# buffers_5bits.net
KiCad netlist of a schematic drawn in Altium Designer
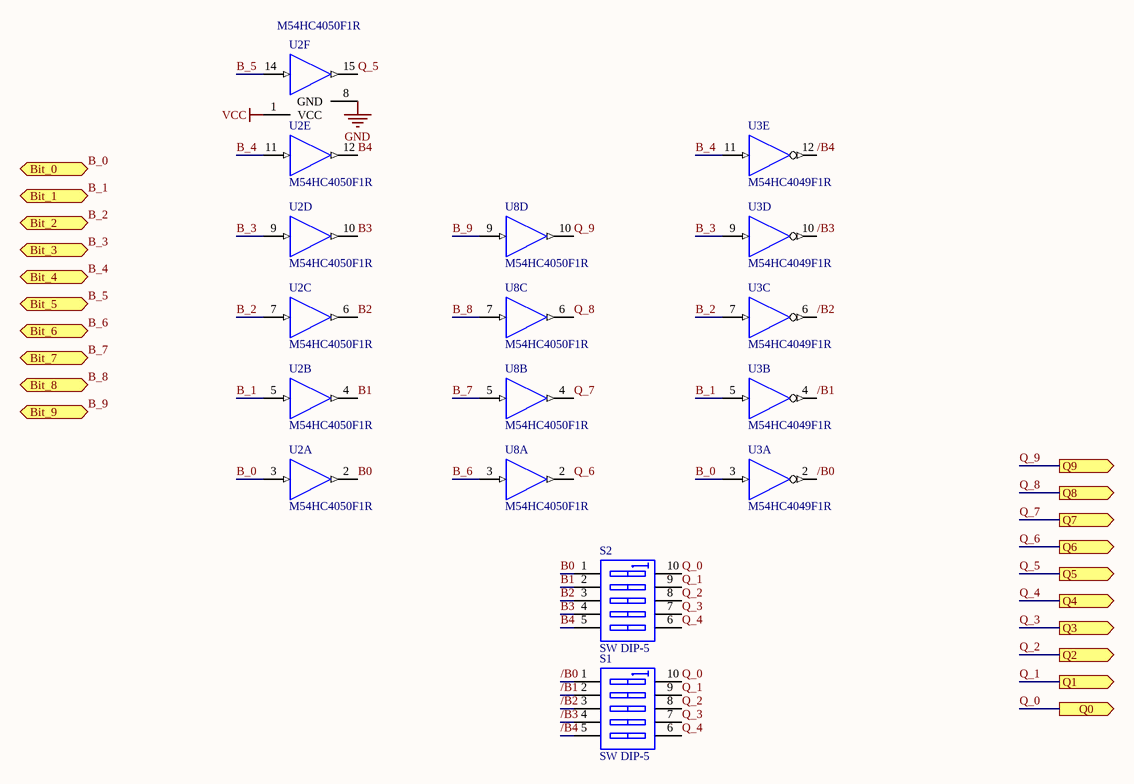
[diagram p0: buffers_5bits.SchDoc]

(export (version "E")
  (design (tool "Eeschema 10.0.6"))
  (components
    (comp (ref "S1")
      (value "SW DIP-5")
      (footprint "N10A")
      (description "DIP Switch, 5 Position, SPST")
      (fields (field (name "PUBLISHER") "Altium Limited"))
      (libsource (lib "Miscellaneous Devices") (part "SW DIP-5"))
    )
    (comp (ref "S2")
      (value "SW DIP-5")
      (footprint "N10A")
      (description "DIP Switch, 5 Position, SPST")
      (fields (field (name "PUBLISHER") "Altium Limited"))
      (libsource (lib "Miscellaneous Devices") (part "SW DIP-5"))
    )
    (comp (ref "U2")
      (value "M54HC4050F1R")
      (footprint "DIP16")
      (description "Hex Buffer/Converter Non-Inverting")
      (fields (field (name "PUBLISHER") "Altium Limited"))
      (libsource (lib "") (part "M54HC4050F1R_1"))
    )
    (comp (ref "U3")
      (value "M54HC4049F1R")
      (footprint "DIP16")
      (description "Hex Buffer/Converter Invertering")
      (fields (field (name "PUBLISHER") "Altium Limited"))
      (libsource (lib "ST Logic Gate") (part "M54HC4049F1R"))
    )
    (comp (ref "U8")
      (value "M54HC4050F1R")
      (footprint "DIP16")
      (description "Hex Buffer/Converter Non-Inverting")
      (fields (field (name "PUBLISHER") "Altium Limited"))
      (libsource (lib "ST Logic Gate") (part "M54HC4050F1R"))
    )
  )
  (nets
    (net (code "1") (name "/B0") (class "Default")
      (node (ref "S2") (pin "1") (pinfunction "A1_1") (pintype "passive"))
      (node (ref "U2") (pin "2") (pinfunction "Y_2") (pintype "output"))
    )
    (net (code "2") (name "/B1") (class "Default")
      (node (ref "S2") (pin "2") (pinfunction "A2_2") (pintype "passive"))
      (node (ref "U2") (pin "4") (pinfunction "Y_4") (pintype "output"))
    )
    (net (code "3") (name "/B2") (class "Default")
      (node (ref "S2") (pin "3") (pinfunction "A3_3") (pintype "passive"))
      (node (ref "U2") (pin "6") (pinfunction "Y_6") (pintype "output"))
    )
    (net (code "4") (name "/B3") (class "Default")
      (node (ref "S2") (pin "4") (pinfunction "A4_4") (pintype "passive"))
      (node (ref "U2") (pin "10") (pinfunction "Y_10") (pintype "output"))
    )
    (net (code "5") (name "/B4") (class "Default")
      (node (ref "S2") (pin "5") (pinfunction "A5_5") (pintype "passive"))
      (node (ref "U2") (pin "12") (pinfunction "Y_12") (pintype "output"))
    )
    (net (code "6") (name "/B_0") (class "Default")
      (node (ref "U2") (pin "3") (pinfunction "A_3") (pintype "input"))
      (node (ref "U3") (pin "3") (pinfunction "A_3") (pintype "input"))
    )
    (net (code "7") (name "/B_1") (class "Default")
      (node (ref "U2") (pin "5") (pinfunction "A_5") (pintype "input"))
      (node (ref "U3") (pin "5") (pinfunction "A_5") (pintype "input"))
    )
    (net (code "8") (name "/B_2") (class "Default")
      (node (ref "U2") (pin "7") (pinfunction "A_7") (pintype "input"))
      (node (ref "U3") (pin "7") (pinfunction "A_7") (pintype "input"))
    )
    (net (code "9") (name "/B_3") (class "Default")
      (node (ref "U2") (pin "9") (pinfunction "A_9") (pintype "input"))
      (node (ref "U3") (pin "9") (pinfunction "A_9") (pintype "input"))
    )
    (net (code "10") (name "/B_4") (class "Default")
      (node (ref "U2") (pin "11") (pinfunction "A_11") (pintype "input"))
      (node (ref "U3") (pin "11") (pinfunction "A_11") (pintype "input"))
    )
    (net (code "11") (name "/B_5") (class "Default")
      (node (ref "U2") (pin "14") (pinfunction "A_14") (pintype "input"))
    )
    (net (code "12") (name "/B_6") (class "Default")
      (node (ref "U8") (pin "3") (pinfunction "A_3") (pintype "input"))
    )
    (net (code "13") (name "/B_7") (class "Default")
      (node (ref "U8") (pin "5") (pinfunction "A_5") (pintype "input"))
    )
    (net (code "14") (name "/B_8") (class "Default")
      (node (ref "U8") (pin "7") (pinfunction "A_7") (pintype "input"))
    )
    (net (code "15") (name "/B_9") (class "Default")
      (node (ref "U8") (pin "9") (pinfunction "A_9") (pintype "input"))
    )
    (net (code "16") (name "/Q_0") (class "Default")
      (node (ref "S1") (pin "10") (pinfunction "B1_10") (pintype "passive"))
      (node (ref "S2") (pin "10") (pinfunction "B1_10") (pintype "passive"))
    )
    (net (code "17") (name "/Q_1") (class "Default")
      (node (ref "S1") (pin "9") (pinfunction "B2_9") (pintype "passive"))
      (node (ref "S2") (pin "9") (pinfunction "B2_9") (pintype "passive"))
    )
    (net (code "18") (name "/Q_2") (class "Default")
      (node (ref "S1") (pin "8") (pinfunction "B3_8") (pintype "passive"))
      (node (ref "S2") (pin "8") (pinfunction "B3_8") (pintype "passive"))
    )
    (net (code "19") (name "/Q_3") (class "Default")
      (node (ref "S1") (pin "7") (pinfunction "B4_7") (pintype "passive"))
      (node (ref "S2") (pin "7") (pinfunction "B4_7") (pintype "passive"))
    )
    (net (code "20") (name "/Q_4") (class "Default")
      (node (ref "S1") (pin "6") (pinfunction "B5_6") (pintype "passive"))
      (node (ref "S2") (pin "6") (pinfunction "B5_6") (pintype "passive"))
    )
    (net (code "21") (name "/Q_5") (class "Default")
      (node (ref "U2") (pin "15") (pinfunction "Y_15") (pintype "output"))
    )
    (net (code "22") (name "/Q_6") (class "Default")
      (node (ref "U8") (pin "2") (pinfunction "Y_2") (pintype "output"))
    )
    (net (code "23") (name "/Q_7") (class "Default")
      (node (ref "U8") (pin "4") (pinfunction "Y_4") (pintype "output"))
    )
    (net (code "24") (name "/Q_8") (class "Default")
      (node (ref "U8") (pin "6") (pinfunction "Y_6") (pintype "output"))
    )
    (net (code "25") (name "/Q_9") (class "Default")
      (node (ref "U8") (pin "10") (pinfunction "Y_10") (pintype "output"))
    )
    (net (code "26") (name "/{slash}B0") (class "Default")
      (node (ref "S1") (pin "1") (pinfunction "A1_1") (pintype "passive"))
      (node (ref "U3") (pin "2") (pinfunction "Y_2") (pintype "output"))
    )
    (net (code "27") (name "/{slash}B1") (class "Default")
      (node (ref "S1") (pin "2") (pinfunction "A2_2") (pintype "passive"))
      (node (ref "U3") (pin "4") (pinfunction "Y_4") (pintype "output"))
    )
    (net (code "28") (name "/{slash}B2") (class "Default")
      (node (ref "S1") (pin "3") (pinfunction "A3_3") (pintype "passive"))
      (node (ref "U3") (pin "6") (pinfunction "Y_6") (pintype "output"))
    )
    (net (code "29") (name "/{slash}B3") (class "Default")
      (node (ref "S1") (pin "4") (pinfunction "A4_4") (pintype "passive"))
      (node (ref "U3") (pin "10") (pinfunction "Y_10") (pintype "output"))
    )
    (net (code "30") (name "/{slash}B4") (class "Default")
      (node (ref "S1") (pin "5") (pinfunction "A5_5") (pintype "passive"))
      (node (ref "U3") (pin "12") (pinfunction "Y_12") (pintype "output"))
    )
    (net (code "31") (name "GND") (class "Default")
      (node (ref "U2") (pin "8") (pinfunction "GND_8") (pintype "power_in"))
      (node (ref "U3") (pin "8") (pinfunction "GND_8") (pintype "power_in"))
      (node (ref "U8") (pin "8") (pinfunction "GND_8") (pintype "power_in"))
    )
    (net (code "32") (name "VCC") (class "Default")
      (node (ref "U2") (pin "1") (pinfunction "VCC_1") (pintype "power_in"))
      (node (ref "U3") (pin "1") (pinfunction "VCC_1") (pintype "power_in"))
      (node (ref "U8") (pin "1") (pinfunction "VCC_1") (pintype "power_in"))
    )
  )
)
